# v_1_0.net
KiCad netlist of a schematic drawn in EAGLE
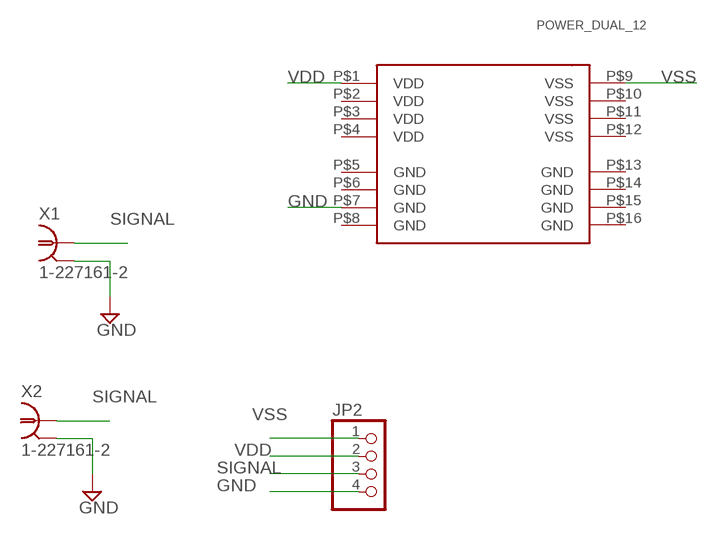
[diagram p0: schematic, sheet 1]

(export (version "E")
  (design (tool "Eeschema 10.0.6"))
  (components
    (comp (ref "JP2")
      (value "PINHD-1X4")
      (footprint "eagle-import:1X04")
      (libsource (lib "eagle-import") (part "PINHD-1X4"))
    )
    (comp (ref "U$1")
      (value "POWER_DUAL_12")
      (footprint "eagle-import:MODULE_4X8")
      (libsource (lib "eagle-import") (part "POWER_DUAL_12"))
    )
    (comp (ref "X1")
      (value "1-227161-2")
      (footprint "eagle-import:AMP_227161")
      (libsource (lib "eagle-import") (part "?2271611--2"))
    )
    (comp (ref "X2")
      (value "1-227161-2")
      (footprint "eagle-import:AMP_227161")
      (libsource (lib "eagle-import") (part "?2271611--2"))
    )
  )
  (nets
    (net (code "1") (name "/SIGNAL") (class "Default")
      (node (ref "JP2") (pin "3") (pinfunction "3_3") (pintype "passive"))
      (node (ref "X1") (pin "1") (pinfunction "1_1") (pintype "passive"))
      (node (ref "X2") (pin "1") (pinfunction "1_1") (pintype "passive"))
    )
    (net (code "2") (name "/VDD") (class "Default")
      (node (ref "JP2") (pin "2") (pinfunction "2_2") (pintype "passive"))
      (node (ref "U$1") (pin "P$1") (pinfunction "VDD_P$1") (pintype "bidirectional"))
    )
    (net (code "3") (name "/VSS") (class "Default")
      (node (ref "JP2") (pin "1") (pinfunction "1_1") (pintype "passive"))
      (node (ref "U$1") (pin "P$9") (pinfunction "VSS_P$9") (pintype "bidirectional"))
    )
    (net (code "4") (name "GND") (class "Default")
      (node (ref "JP2") (pin "4") (pinfunction "4_4") (pintype "passive"))
      (node (ref "U$1") (pin "P$7") (pinfunction "GND_P$7") (pintype "bidirectional"))
      (node (ref "X1") (pin "2") (pinfunction "2_2") (pintype "passive"))
      (node (ref "X2") (pin "2") (pinfunction "2_2") (pintype "passive"))
    )
    (net (code "5") (name "unconnected-(U$1-GND-PadP$5)") (class "Default")
      (node (ref "U$1") (pin "P$5") (pinfunction "GND_P$5") (pintype "bidirectional"))
    )
    (net (code "6") (name "unconnected-(U$1-GND-PadP$6)") (class "Default")
      (node (ref "U$1") (pin "P$6") (pinfunction "GND_P$6") (pintype "bidirectional"))
    )
    (net (code "7") (name "unconnected-(U$1-GND-PadP$8)") (class "Default")
      (node (ref "U$1") (pin "P$8") (pinfunction "GND_P$8") (pintype "bidirectional"))
    )
    (net (code "8") (name "unconnected-(U$1-GND-PadP$13)") (class "Default")
      (node (ref "U$1") (pin "P$13") (pinfunction "GND_P$13") (pintype "bidirectional"))
    )
    (net (code "9") (name "unconnected-(U$1-GND-PadP$14)") (class "Default")
      (node (ref "U$1") (pin "P$14") (pinfunction "GND_P$14") (pintype "bidirectional"))
    )
    (net (code "10") (name "unconnected-(U$1-GND-PadP$15)") (class "Default")
      (node (ref "U$1") (pin "P$15") (pinfunction "GND_P$15") (pintype "bidirectional"))
    )
    (net (code "11") (name "unconnected-(U$1-GND-PadP$16)") (class "Default")
      (node (ref "U$1") (pin "P$16") (pinfunction "GND_P$16") (pintype "bidirectional"))
    )
    (net (code "12") (name "unconnected-(U$1-VDD-PadP$2)") (class "Default")
      (node (ref "U$1") (pin "P$2") (pinfunction "VDD_P$2") (pintype "bidirectional"))
    )
    (net (code "13") (name "unconnected-(U$1-VDD-PadP$3)") (class "Default")
      (node (ref "U$1") (pin "P$3") (pinfunction "VDD_P$3") (pintype "bidirectional"))
    )
    (net (code "14") (name "unconnected-(U$1-VDD-PadP$4)") (class "Default")
      (node (ref "U$1") (pin "P$4") (pinfunction "VDD_P$4") (pintype "bidirectional"))
    )
    (net (code "15") (name "unconnected-(U$1-VSS-PadP$10)") (class "Default")
      (node (ref "U$1") (pin "P$10") (pinfunction "VSS_P$10") (pintype "bidirectional"))
    )
    (net (code "16") (name "unconnected-(U$1-VSS-PadP$11)") (class "Default")
      (node (ref "U$1") (pin "P$11") (pinfunction "VSS_P$11") (pintype "bidirectional"))
    )
    (net (code "17") (name "unconnected-(U$1-VSS-PadP$12)") (class "Default")
      (node (ref "U$1") (pin "P$12") (pinfunction "VSS_P$12") (pintype "bidirectional"))
    )
  )
)
